# SOIC_TSSOP-8_300mil_DIP.net
KiCad netlist of a schematic drawn in EAGLE
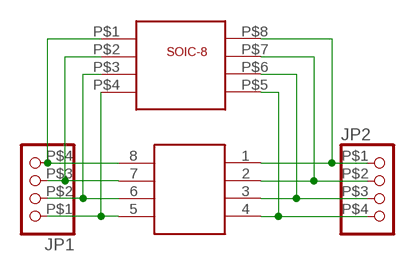
[diagram p0: schematic, sheet 1]

(export (version "E")
  (design (tool "Eeschema 10.0.6"))
  (components
    (comp (ref "JP1")
      (value "PINHD-1X4THIN")
      (footprint "eagle-import:HEADER1X4")
      (libsource (lib "eagle-import") (part "PINHD-1X4THIN"))
    )
    (comp (ref "JP2")
      (value "PINHD-1X4THIN")
      (footprint "eagle-import:HEADER1X4")
      (libsource (lib "eagle-import") (part "PINHD-1X4THIN"))
    )
    (comp (ref "U$1")
      (value "SO-8")
      (footprint "eagle-import:SO-08NMW")
      (libsource (lib "eagle-import") (part "SO-8"))
    )
    (comp (ref "U$2")
      (value "TSSOP-8")
      (footprint "eagle-import:TSSOP-8NM")
      (libsource (lib "eagle-import") (part "TSSOP-8"))
    )
  )
  (nets
    (net (code "1") (name "Net-(JP1-1)") (class "Default")
      (node (ref "JP1") (pin "P$1") (pinfunction "1_P$1") (pintype "passive"))
      (node (ref "U$1") (pin "P$4") (pinfunction "P$4_P$4") (pintype "bidirectional"))
      (node (ref "U$2") (pin "5") (pinfunction "P$5_5") (pintype "bidirectional"))
    )
    (net (code "2") (name "Net-(JP1-2)") (class "Default")
      (node (ref "JP1") (pin "P$2") (pinfunction "2_P$2") (pintype "passive"))
      (node (ref "U$1") (pin "P$3") (pinfunction "P$3_P$3") (pintype "bidirectional"))
      (node (ref "U$2") (pin "6") (pinfunction "P$6_6") (pintype "bidirectional"))
    )
    (net (code "3") (name "Net-(JP1-3)") (class "Default")
      (node (ref "JP1") (pin "P$3") (pinfunction "3_P$3") (pintype "passive"))
      (node (ref "U$1") (pin "P$2") (pinfunction "P$2_P$2") (pintype "bidirectional"))
      (node (ref "U$2") (pin "7") (pinfunction "P$7_7") (pintype "bidirectional"))
    )
    (net (code "4") (name "Net-(JP1-4)") (class "Default")
      (node (ref "JP1") (pin "P$4") (pinfunction "4_P$4") (pintype "passive"))
      (node (ref "U$1") (pin "P$1") (pinfunction "P$1_P$1") (pintype "bidirectional"))
      (node (ref "U$2") (pin "8") (pinfunction "P$8_8") (pintype "bidirectional"))
    )
    (net (code "5") (name "Net-(JP2-1)") (class "Default")
      (node (ref "JP2") (pin "P$1") (pinfunction "1_P$1") (pintype "passive"))
      (node (ref "U$1") (pin "P$8") (pinfunction "P$8_P$8") (pintype "bidirectional"))
      (node (ref "U$2") (pin "1") (pinfunction "P$1_1") (pintype "bidirectional"))
    )
    (net (code "6") (name "Net-(JP2-2)") (class "Default")
      (node (ref "JP2") (pin "P$2") (pinfunction "2_P$2") (pintype "passive"))
      (node (ref "U$1") (pin "P$7") (pinfunction "P$7_P$7") (pintype "bidirectional"))
      (node (ref "U$2") (pin "2") (pinfunction "P$2_2") (pintype "bidirectional"))
    )
    (net (code "7") (name "Net-(JP2-3)") (class "Default")
      (node (ref "JP2") (pin "P$3") (pinfunction "3_P$3") (pintype "passive"))
      (node (ref "U$1") (pin "P$6") (pinfunction "P$6_P$6") (pintype "bidirectional"))
      (node (ref "U$2") (pin "3") (pinfunction "P$3_3") (pintype "bidirectional"))
    )
    (net (code "8") (name "Net-(JP2-4)") (class "Default")
      (node (ref "JP2") (pin "P$4") (pinfunction "4_P$4") (pintype "passive"))
      (node (ref "U$1") (pin "P$5") (pinfunction "P$5_P$5") (pintype "bidirectional"))
      (node (ref "U$2") (pin "4") (pinfunction "P$4_4") (pintype "bidirectional"))
    )
  )
)
